# Sheet1.net
KiCad netlist of a schematic drawn in Altium Designer
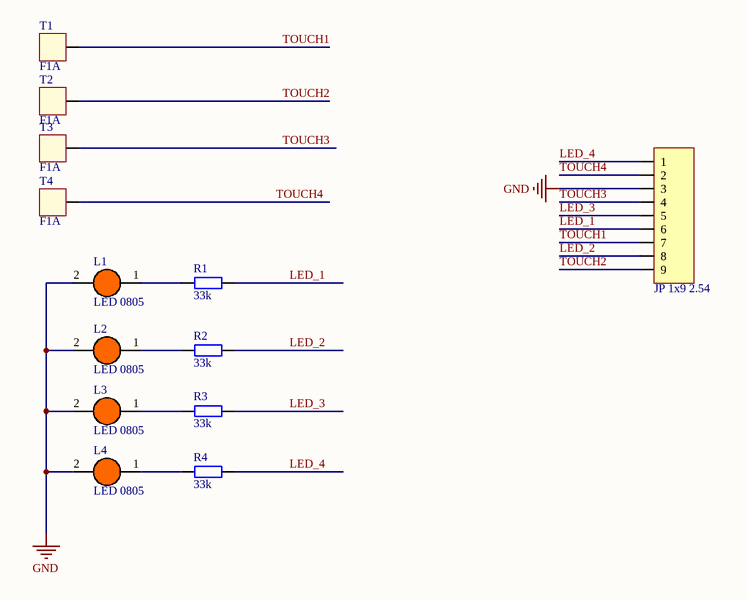
[diagram p0: Sheet1.SchDoc]

(export (version "E")
  (design (tool "Eeschema 10.0.6"))
  (components
    (comp (ref "JP1")
      (value "JP 1x9 2.54")
      (footprint "JP 1x9 CT")
      (description "Cắm")
      (libsource (lib "Altium_Lib_by_KhueNguyenCreator") (part "JP 1x9 2.54 Cai Thang"))
    )
    (comp (ref "L1")
      (value "LED 0805")
      (footprint "LED-0805-Orange")
      (description "Dán")
      (libsource (lib "Altium_Lib_by_KhueNguyenCreator") (part "LED 0805 Cam"))
    )
    (comp (ref "L2")
      (value "LED 0805")
      (footprint "LED-0805-Orange")
      (description "Dán")
      (libsource (lib "Altium_Lib_by_KhueNguyenCreator") (part "LED 0805 Cam"))
    )
    (comp (ref "L3")
      (value "LED 0805")
      (footprint "LED-0805-Orange")
      (description "Dán")
      (libsource (lib "Altium_Lib_by_KhueNguyenCreator") (part "LED 0805 Cam"))
    )
    (comp (ref "L4")
      (value "LED 0805")
      (footprint "LED-0805-Orange")
      (description "Dán")
      (libsource (lib "Altium_Lib_by_KhueNguyenCreator") (part "LED 0805 Cam"))
    )
    (comp (ref "R1")
      (value "33k")
      (footprint "tro smd 0805")
      (description "Dán")
      (libsource (lib "Altium_Lib_by_KhueNguyenCreator") (part "Tro 0805 1% 33k"))
    )
    (comp (ref "R2")
      (value "33k")
      (footprint "tro smd 0805")
      (description "Dán")
      (libsource (lib "Altium_Lib_by_KhueNguyenCreator") (part "Tro 0805 1% 33k"))
    )
    (comp (ref "R3")
      (value "33k")
      (footprint "tro smd 0805")
      (description "Dán")
      (libsource (lib "Altium_Lib_by_KhueNguyenCreator") (part "Tro 0805 1% 33k"))
    )
    (comp (ref "R4")
      (value "33k")
      (footprint "tro smd 0805")
      (description "Dán")
      (libsource (lib "Altium_Lib_by_KhueNguyenCreator") (part "Tro 0805 1% 33k"))
    )
    (comp (ref "T1")
      (value "F1A")
      (footprint "Touch")
      (description "Fuse")
      (fields (field (name "DESIGNED BY") "VanDungEvn"))
      (libsource (lib "myLib_v1") (part "Touch"))
    )
    (comp (ref "T2")
      (value "F1A")
      (footprint "Touch")
      (description "Fuse")
      (fields (field (name "DESIGNED BY") "VanDungEvn"))
      (libsource (lib "myLib_v1") (part "Touch"))
    )
    (comp (ref "T3")
      (value "F1A")
      (footprint "Touch")
      (description "Fuse")
      (fields (field (name "DESIGNED BY") "VanDungEvn"))
      (libsource (lib "myLib_v1") (part "Touch"))
    )
    (comp (ref "T4")
      (value "F1A")
      (footprint "Touch")
      (description "Fuse")
      (fields (field (name "DESIGNED BY") "VanDungEvn"))
      (libsource (lib "myLib_v1") (part "Touch"))
    )
  )
  (nets
    (net (code "1") (name "/LED_1") (class "Default")
      (node (ref "JP1") (pin "6") (pinfunction "6_6") (pintype "passive"))
      (node (ref "R1") (pin "1") (pinfunction "1_1") (pintype "passive"))
    )
    (net (code "2") (name "/LED_2") (class "Default")
      (node (ref "JP1") (pin "8") (pinfunction "8_8") (pintype "passive"))
      (node (ref "R2") (pin "1") (pinfunction "1_1") (pintype "passive"))
    )
    (net (code "3") (name "/LED_3") (class "Default")
      (node (ref "JP1") (pin "5") (pinfunction "5_5") (pintype "passive"))
      (node (ref "R3") (pin "1") (pinfunction "1_1") (pintype "passive"))
    )
    (net (code "4") (name "/LED_4") (class "Default")
      (node (ref "JP1") (pin "1") (pinfunction "1_1") (pintype "passive"))
      (node (ref "R4") (pin "1") (pinfunction "1_1") (pintype "passive"))
    )
    (net (code "5") (name "/TOUCH1") (class "Default")
      (node (ref "JP1") (pin "7") (pinfunction "7_7") (pintype "passive"))
      (node (ref "T1") (pin "1") (pinfunction "1_1") (pintype "passive"))
    )
    (net (code "6") (name "/TOUCH2") (class "Default")
      (node (ref "JP1") (pin "9") (pinfunction "9_9") (pintype "passive"))
      (node (ref "T2") (pin "1") (pinfunction "1_1") (pintype "passive"))
    )
    (net (code "7") (name "/TOUCH3") (class "Default")
      (node (ref "JP1") (pin "4") (pinfunction "4_4") (pintype "passive"))
      (node (ref "T3") (pin "1") (pinfunction "1_1") (pintype "passive"))
    )
    (net (code "8") (name "/TOUCH4") (class "Default")
      (node (ref "JP1") (pin "2") (pinfunction "2_2") (pintype "passive"))
      (node (ref "T4") (pin "1") (pinfunction "1_1") (pintype "passive"))
    )
    (net (code "9") (name "GND") (class "Default")
      (node (ref "JP1") (pin "3") (pinfunction "3_3") (pintype "passive"))
      (node (ref "L1") (pin "2") (pinfunction "K_2") (pintype "passive"))
      (node (ref "L2") (pin "2") (pinfunction "K_2") (pintype "passive"))
      (node (ref "L3") (pin "2") (pinfunction "K_2") (pintype "passive"))
      (node (ref "L4") (pin "2") (pinfunction "K_2") (pintype "passive"))
    )
    (net (code "10") (name "Net-(L1-A)") (class "Default")
      (node (ref "L1") (pin "1") (pinfunction "A_1") (pintype "passive"))
      (node (ref "R1") (pin "2") (pinfunction "2_2") (pintype "passive"))
    )
    (net (code "11") (name "Net-(L2-A)") (class "Default")
      (node (ref "L2") (pin "1") (pinfunction "A_1") (pintype "passive"))
      (node (ref "R2") (pin "2") (pinfunction "2_2") (pintype "passive"))
    )
    (net (code "12") (name "Net-(L3-A)") (class "Default")
      (node (ref "L3") (pin "1") (pinfunction "A_1") (pintype "passive"))
      (node (ref "R3") (pin "2") (pinfunction "2_2") (pintype "passive"))
    )
    (net (code "13") (name "Net-(L4-A)") (class "Default")
      (node (ref "L4") (pin "1") (pinfunction "A_1") (pintype "passive"))
      (node (ref "R4") (pin "2") (pinfunction "2_2") (pintype "passive"))
    )
  )
)
